# SuperScampSchematic.net
KiCad netlist of a schematic drawn in Altium Designer
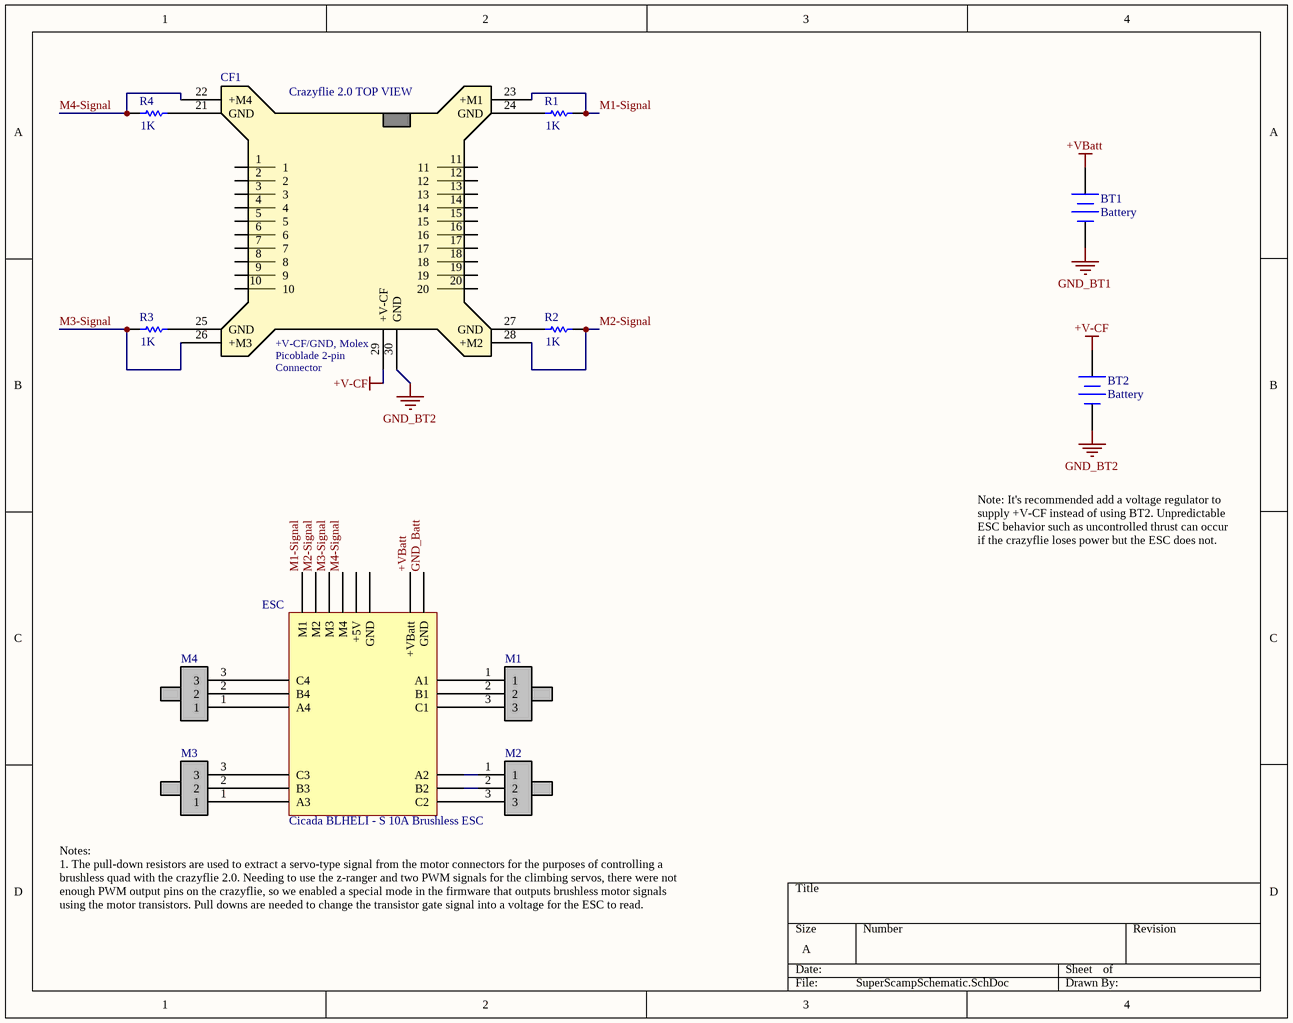
[diagram p0: SuperScampSchematic.SchDoc]

(export (version "E")
  (design (tool "Eeschema 10.0.6"))
  (components
    (comp (ref "BT1")
      (value "Battery")
      (footprint "BAT-2")
      (description "Multicell Battery")
      (fields (field (name "PUBLISHER") "Altium Limited"))
      (libsource (lib "Miscellaneous Devices") (part "Battery"))
    )
    (comp (ref "BT2")
      (value "Battery")
      (footprint "BAT-2")
      (description "Multicell Battery")
      (fields (field (name "PUBLISHER") "Altium Limited"))
      (libsource (lib "Miscellaneous Devices") (part "Battery"))
    )
    (comp (ref "CF1") (value "Crazyflie 2.0") (libsource (lib "SuperScamp") (part "Crazyflie 2.0")))
    (comp (ref "ESC")
      (value "Cicada BLHELI - S 10A Brushless ESC")
      (libsource (lib "SuperScamp") (part "Cicada BLHELI - S 10A Brushless ESC"))
    )
    (comp (ref "M1") (value "M?") (libsource (lib "SuperScamp") (part "DYS BE1104")))
    (comp (ref "M2") (value "M?") (libsource (lib "SuperScamp") (part "DYS BE1104")))
    (comp (ref "M3") (value "M?") (libsource (lib "") (part "DYS BE1104_1")))
    (comp (ref "M4") (value "M?") (libsource (lib "") (part "DYS BE1104_1")))
    (comp (ref "R1")
      (value "1K")
      (footprint "AXIAL-0.3")
      (description "Resistor")
      (fields (field (name "Comment") "Res1") (field (name "PUBLISHER") "Altium Limited"))
      (libsource (lib "Miscellaneous Devices") (part "Res1"))
    )
    (comp (ref "R2")
      (value "1K")
      (footprint "AXIAL-0.3")
      (description "Resistor")
      (fields (field (name "Comment") "Res1") (field (name "PUBLISHER") "Altium Limited"))
      (libsource (lib "Miscellaneous Devices") (part "Res1"))
    )
    (comp (ref "R3")
      (value "1K")
      (footprint "AXIAL-0.3")
      (description "Resistor")
      (fields (field (name "Comment") "Res1") (field (name "PUBLISHER") "Altium Limited"))
      (libsource (lib "Miscellaneous Devices") (part "Res1"))
    )
    (comp (ref "R4")
      (value "1K")
      (footprint "AXIAL-0.3")
      (description "Resistor")
      (fields (field (name "Comment") "Res1") (field (name "PUBLISHER") "Altium Limited"))
      (libsource (lib "Miscellaneous Devices") (part "Res1"))
    )
  )
  (nets
    (net (code "1") (name "+V-CF") (class "Default")
      (node (ref "BT2") (pin "1") (pinfunction "+_1") (pintype "passive"))
      (node (ref "CF1") (pin "29") (pinfunction "+V-CF_29") (pintype "passive"))
    )
    (net (code "2") (name "+VBatt") (class "Default")
      (node (ref "BT1") (pin "1") (pinfunction "+_1") (pintype "passive"))
      (node (ref "ESC") (pin "18") (pinfunction "+VBatt_18") (pintype "passive"))
    )
    (net (code "3") (name "/GND_Batt") (class "Default")
      (node (ref "ESC") (pin "19") (pinfunction "GND_19") (pintype "passive"))
    )
    (net (code "4") (name "/M1-Signal") (class "Default")
      (node (ref "CF1") (pin "23") (pinfunction "+M1_23") (pintype "passive"))
      (node (ref "ESC") (pin "13") (pinfunction "M1_13") (pintype "passive"))
      (node (ref "R1") (pin "2") (pinfunction "2_2") (pintype "passive"))
    )
    (net (code "5") (name "/M2-Signal") (class "Default")
      (node (ref "CF1") (pin "28") (pinfunction "+M2_28") (pintype "passive"))
      (node (ref "ESC") (pin "14") (pinfunction "M2_14") (pintype "passive"))
      (node (ref "R2") (pin "2") (pinfunction "2_2") (pintype "passive"))
    )
    (net (code "6") (name "/M3-Signal") (class "Default")
      (node (ref "CF1") (pin "26") (pinfunction "+M3_26") (pintype "passive"))
      (node (ref "ESC") (pin "15") (pinfunction "M3_15") (pintype "passive"))
      (node (ref "R3") (pin "1") (pinfunction "1_1") (pintype "passive"))
    )
    (net (code "7") (name "/M4-Signal") (class "Default")
      (node (ref "CF1") (pin "22") (pinfunction "+M4_22") (pintype "passive"))
      (node (ref "ESC") (pin "16") (pinfunction "M4_16") (pintype "passive"))
      (node (ref "R4") (pin "1") (pinfunction "1_1") (pintype "passive"))
    )
    (net (code "8") (name "GND_BT1") (class "Default")
      (node (ref "BT1") (pin "2") (pinfunction "-_2") (pintype "passive"))
    )
    (net (code "9") (name "GND_BT2") (class "Default")
      (node (ref "BT2") (pin "2") (pinfunction "-_2") (pintype "passive"))
      (node (ref "CF1") (pin "30") (pinfunction "GND_30") (pintype "passive"))
    )
    (net (code "10") (name "Net-(CF1-GND-Pad21)") (class "Default")
      (node (ref "CF1") (pin "21") (pinfunction "GND_21") (pintype "passive"))
      (node (ref "R4") (pin "2") (pinfunction "2_2") (pintype "passive"))
    )
    (net (code "11") (name "Net-(CF1-GND-Pad24)") (class "Default")
      (node (ref "CF1") (pin "24") (pinfunction "GND_24") (pintype "passive"))
      (node (ref "R1") (pin "1") (pinfunction "1_1") (pintype "passive"))
    )
    (net (code "12") (name "Net-(CF1-GND-Pad25)") (class "Default")
      (node (ref "CF1") (pin "25") (pinfunction "GND_25") (pintype "passive"))
      (node (ref "R3") (pin "2") (pinfunction "2_2") (pintype "passive"))
    )
    (net (code "13") (name "Net-(CF1-GND-Pad27)") (class "Default")
      (node (ref "CF1") (pin "27") (pinfunction "GND_27") (pintype "passive"))
      (node (ref "R2") (pin "1") (pinfunction "1_1") (pintype "passive"))
    )
    (net (code "14") (name "Net-(ESC-A2)") (class "Default")
      (node (ref "ESC") (pin "4") (pinfunction "A2_4") (pintype "passive"))
      (node (ref "M2") (pin "1") (pinfunction "1_1") (pintype "passive"))
    )
    (net (code "15") (name "Net-(ESC-A3)") (class "Default")
      (node (ref "ESC") (pin "7") (pinfunction "A3_7") (pintype "passive"))
      (node (ref "M3") (pin "1") (pinfunction "1_1") (pintype "passive"))
    )
    (net (code "16") (name "Net-(ESC-A4)") (class "Default")
      (node (ref "ESC") (pin "10") (pinfunction "A4_10") (pintype "passive"))
      (node (ref "M4") (pin "1") (pinfunction "1_1") (pintype "passive"))
    )
    (net (code "17") (name "Net-(ESC-B2)") (class "Default")
      (node (ref "ESC") (pin "5") (pinfunction "B2_5") (pintype "passive"))
      (node (ref "M2") (pin "2") (pinfunction "2_2") (pintype "passive"))
    )
    (net (code "18") (name "Net-(ESC-B3)") (class "Default")
      (node (ref "ESC") (pin "8") (pinfunction "B3_8") (pintype "passive"))
      (node (ref "M3") (pin "2") (pinfunction "2_2") (pintype "passive"))
    )
    (net (code "19") (name "Net-(ESC-B4)") (class "Default")
      (node (ref "ESC") (pin "11") (pinfunction "B4_11") (pintype "passive"))
      (node (ref "M4") (pin "2") (pinfunction "2_2") (pintype "passive"))
    )
    (net (code "20") (name "Net-(ESC-C3)") (class "Default")
      (node (ref "ESC") (pin "9") (pinfunction "C3_9") (pintype "passive"))
      (node (ref "M3") (pin "3") (pinfunction "3_3") (pintype "passive"))
    )
    (net (code "21") (name "Net-(ESC-C4)") (class "Default")
      (node (ref "ESC") (pin "12") (pinfunction "C4_12") (pintype "passive"))
      (node (ref "M4") (pin "3") (pinfunction "3_3") (pintype "passive"))
    )
    (net (code "22") (name "unconnected-(CF1-Pad1)") (class "Default")
      (node (ref "CF1") (pin "1") (pinfunction "1_1") (pintype "passive"))
    )
    (net (code "23") (name "unconnected-(CF1-Pad2)") (class "Default")
      (node (ref "CF1") (pin "2") (pinfunction "2_2") (pintype "passive"))
    )
    (net (code "24") (name "unconnected-(CF1-Pad3)") (class "Default")
      (node (ref "CF1") (pin "3") (pinfunction "3_3") (pintype "passive"))
    )
    (net (code "25") (name "unconnected-(CF1-Pad4)") (class "Default")
      (node (ref "CF1") (pin "4") (pinfunction "4_4") (pintype "passive"))
    )
    (net (code "26") (name "unconnected-(CF1-Pad5)") (class "Default")
      (node (ref "CF1") (pin "5") (pinfunction "5_5") (pintype "passive"))
    )
    (net (code "27") (name "unconnected-(CF1-Pad6)") (class "Default")
      (node (ref "CF1") (pin "6") (pinfunction "6_6") (pintype "passive"))
    )
    (net (code "28") (name "unconnected-(CF1-Pad7)") (class "Default")
      (node (ref "CF1") (pin "7") (pinfunction "7_7") (pintype "passive"))
    )
    (net (code "29") (name "unconnected-(CF1-Pad8)") (class "Default")
      (node (ref "CF1") (pin "8") (pinfunction "8_8") (pintype "passive"))
    )
    (net (code "30") (name "unconnected-(CF1-Pad9)") (class "Default")
      (node (ref "CF1") (pin "9") (pinfunction "9_9") (pintype "passive"))
    )
    (net (code "31") (name "unconnected-(CF1-Pad10)") (class "Default")
      (node (ref "CF1") (pin "10") (pinfunction "10_10") (pintype "passive"))
    )
    (net (code "32") (name "unconnected-(CF1-Pad11)") (class "Default")
      (node (ref "CF1") (pin "11") (pinfunction "11_11") (pintype "passive"))
    )
    (net (code "33") (name "unconnected-(CF1-Pad12)") (class "Default")
      (node (ref "CF1") (pin "12") (pinfunction "12_12") (pintype "passive"))
    )
    (net (code "34") (name "unconnected-(CF1-Pad13)") (class "Default")
      (node (ref "CF1") (pin "13") (pinfunction "13_13") (pintype "passive"))
    )
    (net (code "35") (name "unconnected-(CF1-Pad14)") (class "Default")
      (node (ref "CF1") (pin "14") (pinfunction "14_14") (pintype "passive"))
    )
    (net (code "36") (name "unconnected-(CF1-Pad15)") (class "Default")
      (node (ref "CF1") (pin "15") (pinfunction "15_15") (pintype "passive"))
    )
    (net (code "37") (name "unconnected-(CF1-Pad16)") (class "Default")
      (node (ref "CF1") (pin "16") (pinfunction "16_16") (pintype "passive"))
    )
    (net (code "38") (name "unconnected-(CF1-Pad17)") (class "Default")
      (node (ref "CF1") (pin "17") (pinfunction "17_17") (pintype "passive"))
    )
    (net (code "39") (name "unconnected-(CF1-Pad18)") (class "Default")
      (node (ref "CF1") (pin "18") (pinfunction "18_18") (pintype "passive"))
    )
    (net (code "40") (name "unconnected-(CF1-Pad19)") (class "Default")
      (node (ref "CF1") (pin "19") (pinfunction "19_19") (pintype "passive"))
    )
    (net (code "41") (name "unconnected-(CF1-Pad20)") (class "Default")
      (node (ref "CF1") (pin "20") (pinfunction "20_20") (pintype "passive"))
    )
    (net (code "42") (name "unconnected-(ESC-+5V-Pad17)") (class "Default")
      (node (ref "ESC") (pin "17") (pinfunction "+5V_17") (pintype "passive"))
    )
    (net (code "43") (name "unconnected-(ESC-A1-Pad1)") (class "Default")
      (node (ref "ESC") (pin "1") (pinfunction "A1_1") (pintype "passive"))
    )
    (net (code "44") (name "unconnected-(ESC-B1-Pad2)") (class "Default")
      (node (ref "ESC") (pin "2") (pinfunction "B1_2") (pintype "passive"))
    )
    (net (code "45") (name "unconnected-(ESC-C1-Pad3)") (class "Default")
      (node (ref "ESC") (pin "3") (pinfunction "C1_3") (pintype "passive"))
    )
    (net (code "46") (name "unconnected-(ESC-C2-Pad6)") (class "Default")
      (node (ref "ESC") (pin "6") (pinfunction "C2_6") (pintype "passive"))
    )
    (net (code "47") (name "unconnected-(ESC-GND-Pad18)") (class "Default")
      (node (ref "ESC") (pin "18") (pinfunction "GND_18") (pintype "passive"))
    )
    (net (code "48") (name "unconnected-(M1-Pad1)") (class "Default")
      (node (ref "M1") (pin "1") (pinfunction "1_1") (pintype "passive"))
    )
    (net (code "49") (name "unconnected-(M1-Pad2)") (class "Default")
      (node (ref "M1") (pin "2") (pinfunction "2_2") (pintype "passive"))
    )
    (net (code "50") (name "unconnected-(M1-Pad3)") (class "Default")
      (node (ref "M1") (pin "3") (pinfunction "3_3") (pintype "passive"))
    )
    (net (code "51") (name "unconnected-(M2-Pad3)") (class "Default")
      (node (ref "M2") (pin "3") (pinfunction "3_3") (pintype "passive"))
    )
  )
)
